# SCH_CanSat2024_v5_1.net
KiCad netlist of a schematic drawn in EasyEDA
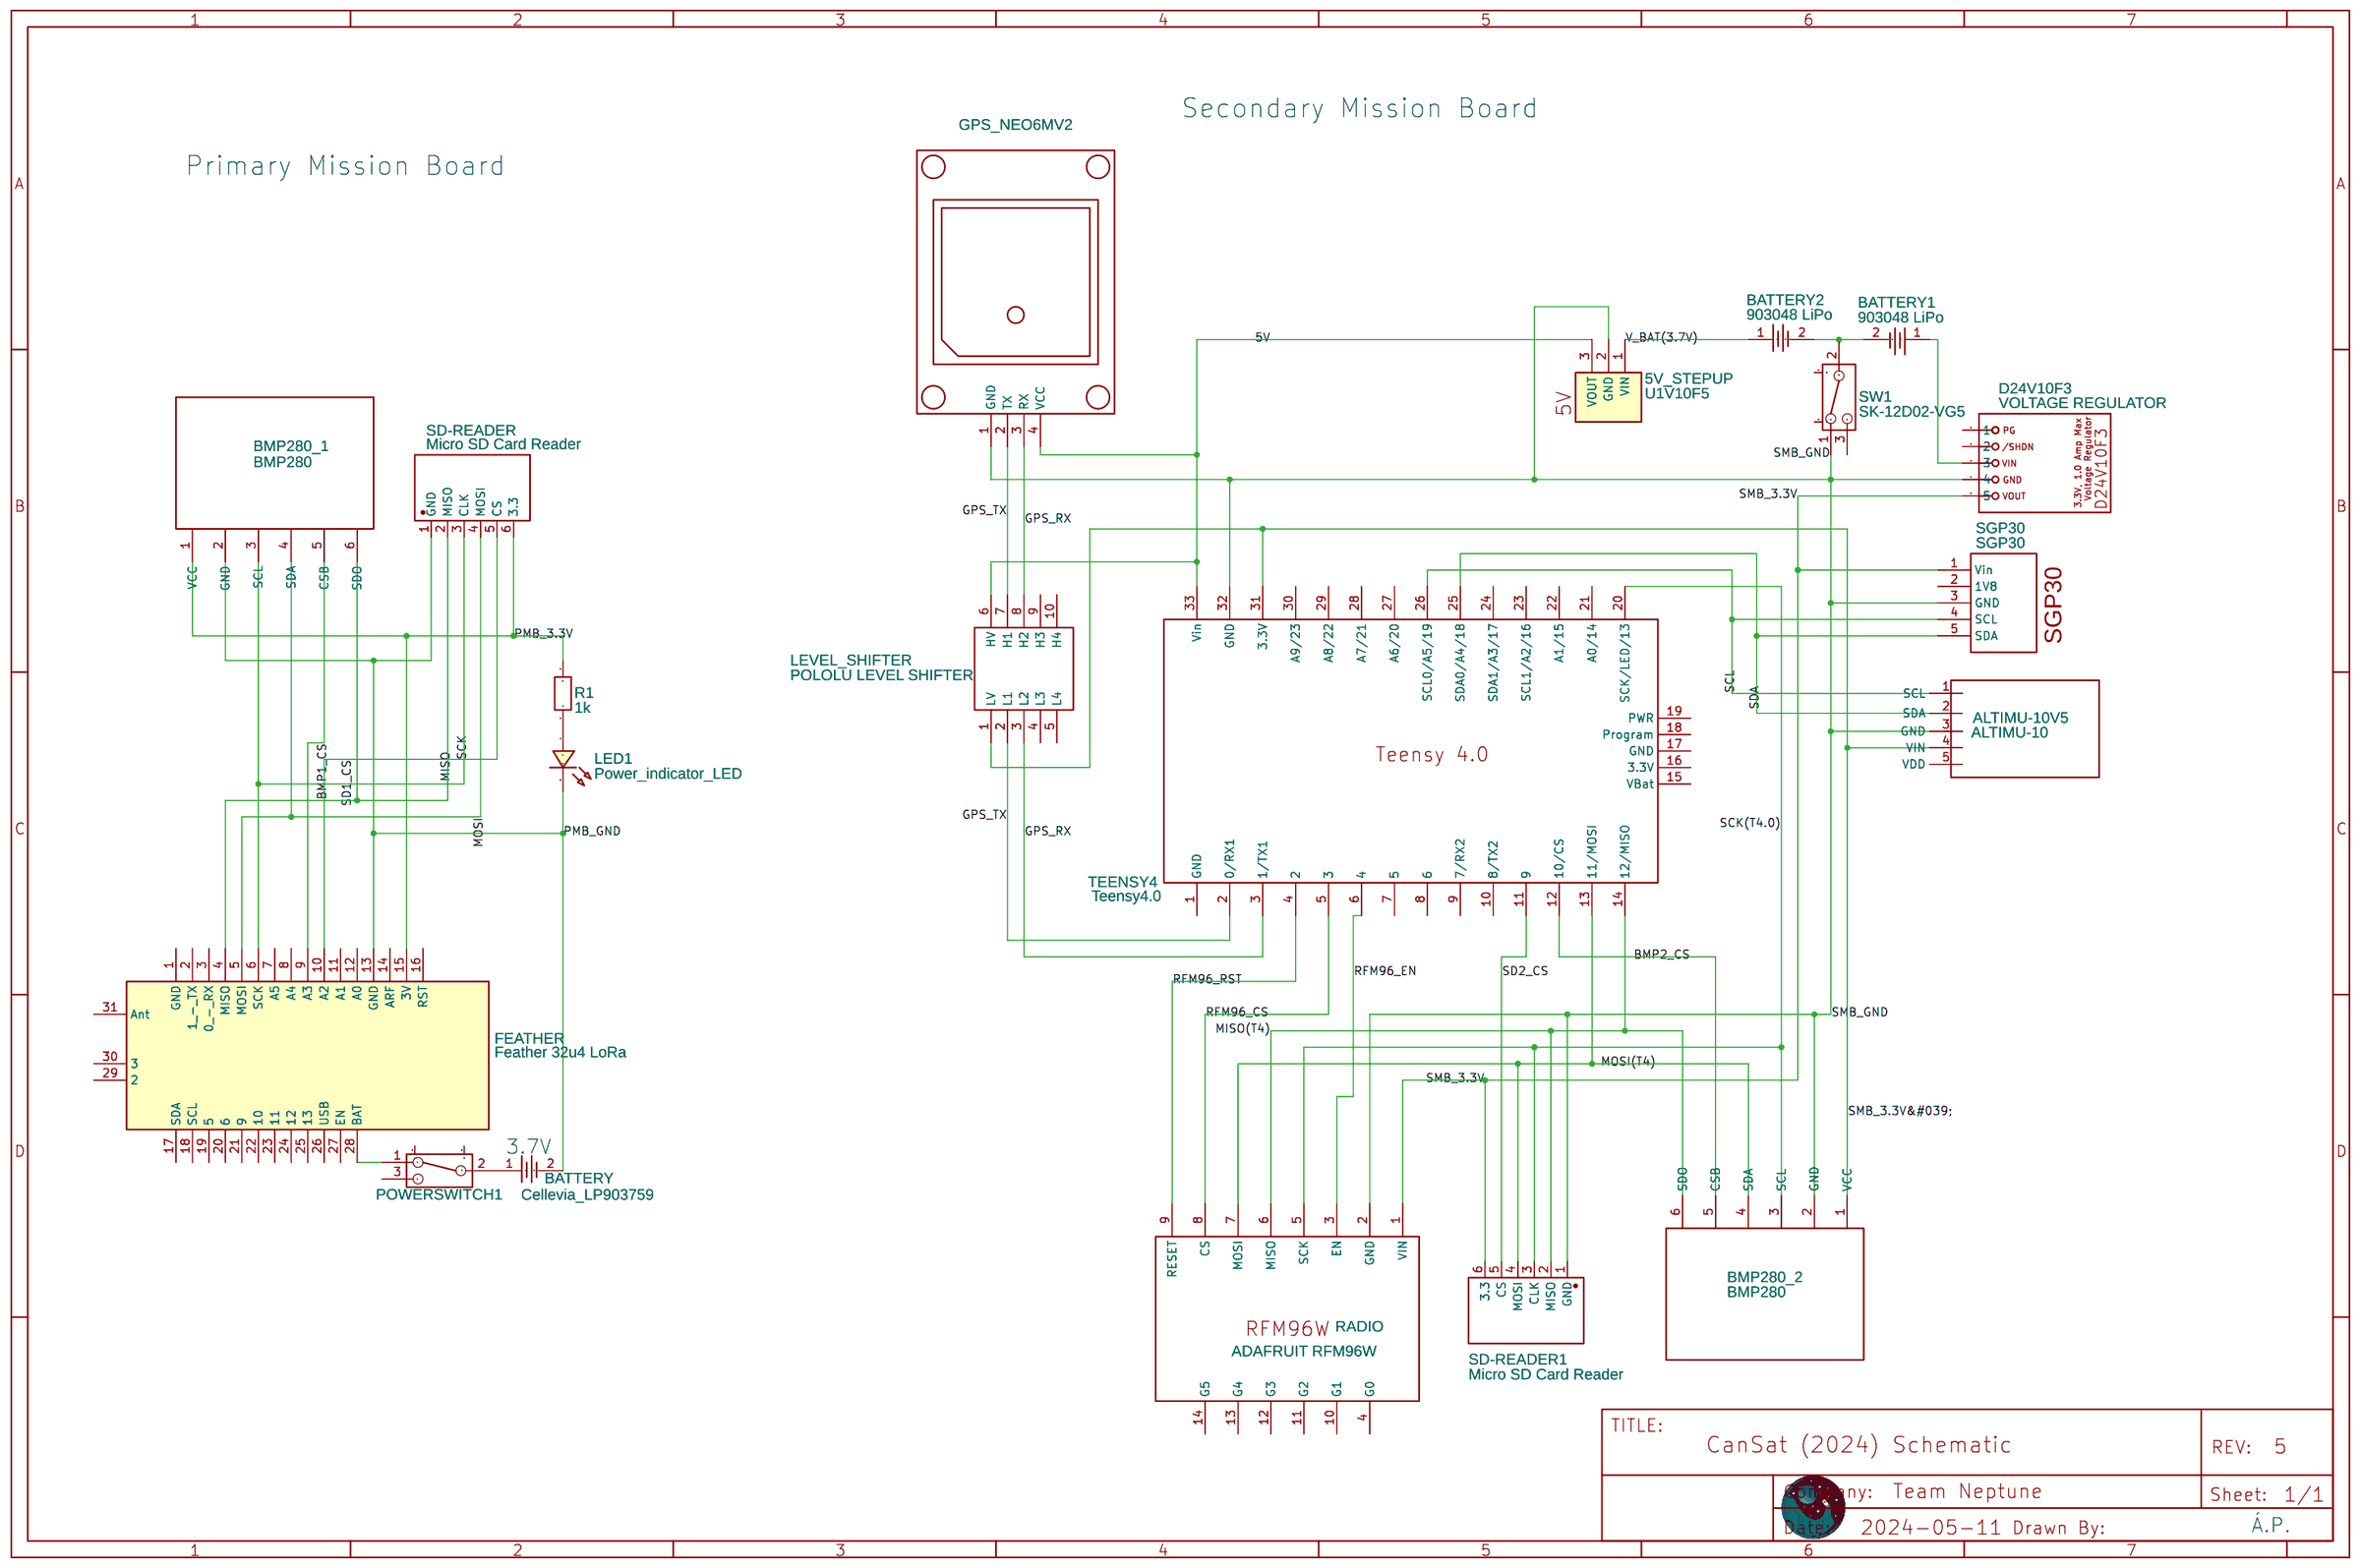
[diagram p0: schematic sheet]

(export (version "E")
  (design (tool "Eeschema 10.0.6"))
  (components
    (comp (ref "5V_STEPUP") (value "U1V10F5") (libsource (lib "") (part "U1V10F5 COPY")))
    (comp (ref "ALTIMU-10V5") (value "ALTIMU-10") (libsource (lib "") (part "ALTIMU-10")))
    (comp (ref "BATTERY")
      (value "Cellevia_LP903759")
      (fields (field (name "Manufacturer Part") "CR1220-2") (field (name "Manufacturer") "Q&J"))
      (libsource (lib "") (part "CR1220-2"))
    )
    (comp (ref "BATTERY1")
      (value "903048 LiPo")
      (fields (field (name "Manufacturer Part") "CR1220-2") (field (name "Manufacturer") "Q&J"))
      (libsource (lib "") (part "CR1220-2_1"))
    )
    (comp (ref "BATTERY2")
      (value "903048 LiPo")
      (fields (field (name "Manufacturer Part") "CR1220-2") (field (name "Manufacturer") "Q&J"))
      (libsource (lib "") (part "CR1220-2"))
    )
    (comp (ref "BMP280_1") (value "BMP280") (libsource (lib "") (part "BMP280_1")))
    (comp (ref "BMP280_2") (value "BMP280") (libsource (lib "") (part "BMP280")))
    (comp (ref "D24V10F3")
      (value "VOLTAGE REGULATOR")
      (fields (field (name "Manufacturer Part") "HDR-M-2.54_1x6"))
      (libsource (lib "") (part "D24V10F5 VOLTAGE REGULATOR"))
    )
    (comp (ref "FEATHER") (value "Feather 32u4 LoRa") (libsource (lib "") (part "Feather 32u4 LoRa")))
    (comp (ref "GPS_NEO6MV2") (value "Cheap GPS") (libsource (lib "") (part "Cheap GPS")))
    (comp (ref "LED1")
      (value "Power_indicator_LED")
      (fields
        (field (name "Manufacturer Part") "19-217/R6C-AL1M2VY/3T")
        (field (name "Manufacturer") "EVERLIGHT(台湾亿光)")
      )
      (libsource (lib "") (part "LED-0603_R"))
    )
    (comp (ref "LEVEL_SHIFTER")
      (value "POLOLU LEVEL SHIFTER")
      (fields (field (name "Manufacturer Part") "pololu #2595") (field (name "Manufacturer") "POLOLU"))
      (libsource (lib "") (part "pololu_level_shifter"))
    )
    (comp (ref "POWERSWITCH1")
      (value "SWITCH")
      (fields
        (field (name "Manufacturer Part") "SK-12D02-VG5")
        (field (name "Manufacturer") "Rectangular Connectors - Contacts")
      )
      (libsource (lib "") (part "SK-12D02-VG5_1"))
    )
    (comp (ref "R1") (value "1k") (libsource (lib "") (part "R_0603_EU")))
    (comp (ref "RADIO")
      (value "ADAFRUIT RFM96W")
      (fields (field (name "Manufacturer Part") "RFM96W") (field (name "Manufacturer") "HopeRF"))
      (libsource (lib "") (part "ADAFRUIT RFM96W BOARD COPY"))
    )
    (comp (ref "SD-READER")
      (value "Micro SD Card Reader")
      (fields
        (field (name "Manufacturer Part") "SD card reader 17.9x17.9")
        (field (name "Manufacturer") "ShengYang")
      )
      (libsource (lib "") (part "Micro SD Card Reader_1"))
    )
    (comp (ref "SD-READER1")
      (value "Micro SD Card Reader")
      (fields
        (field (name "Manufacturer Part") "SD card reader 17.9x17.9")
        (field (name "Manufacturer") "ShengYang")
      )
      (libsource (lib "") (part "Micro SD Card Reader"))
    )
    (comp (ref "SGP30")
      (value "SGP30")
      (fields (field (name "Manufacturer Part") "Adafruit"))
      (libsource (lib "") (part "SGP30"))
    )
    (comp (ref "SW1")
      (value "SK-12D02-VG5")
      (fields (field (name "Manufacturer") "Rectangular Connectors - Contacts"))
      (libsource (lib "") (part "SK-12D02-VG5"))
    )
    (comp (ref "TEENSY4")
      (value "Teensy4.0")
      (fields (field (name "Manufacturer") "PJRC"))
      (libsource (lib "") (part "Teensy4.0"))
    )
  )
  (nets
    (net (code "1") (name "/5V") (class "Default")
      (node (ref "5V_STEPUP") (pin "3") (pinfunction "VOUT_3") (pintype "unspecified"))
      (node (ref "GPS_NEO6MV2") (pin "4") (pinfunction "VCC_4") (pintype "unspecified"))
      (node (ref "LEVEL_SHIFTER") (pin "6") (pinfunction "HV_6") (pintype "unspecified"))
      (node (ref "TEENSY4") (pin "33") (pinfunction "Vin_33") (pintype "unspecified"))
    )
    (net (code "2") (name "/BMP1_CS") (class "Default")
      (node (ref "BMP280_1") (pin "5") (pinfunction "CSB_5") (pintype "unspecified"))
      (node (ref "FEATHER") (pin "9") (pinfunction "A3_9") (pintype "unspecified"))
    )
    (net (code "3") (name "/BMP2_CS") (class "Default")
      (node (ref "BMP280_2") (pin "5") (pinfunction "CSB_5") (pintype "unspecified"))
      (node (ref "TEENSY4") (pin "12") (pinfunction "10/CS_12") (pintype "unspecified"))
    )
    (net (code "4") (name "/GPS_RX") (class "Default")
      (node (ref "GPS_NEO6MV2") (pin "3") (pinfunction "RX_3") (pintype "unspecified"))
      (node (ref "LEVEL_SHIFTER") (pin "3") (pinfunction "L2_3") (pintype "unspecified"))
      (node (ref "LEVEL_SHIFTER") (pin "8") (pinfunction "H2_8") (pintype "unspecified"))
      (node (ref "TEENSY4") (pin "3") (pinfunction "1/TX1_3") (pintype "unspecified"))
    )
    (net (code "5") (name "/GPS_TX") (class "Default")
      (node (ref "GPS_NEO6MV2") (pin "2") (pinfunction "TX_2") (pintype "unspecified"))
      (node (ref "LEVEL_SHIFTER") (pin "2") (pinfunction "L1_2") (pintype "unspecified"))
      (node (ref "LEVEL_SHIFTER") (pin "7") (pinfunction "H1_7") (pintype "unspecified"))
      (node (ref "TEENSY4") (pin "2") (pinfunction "0/RX1_2") (pintype "unspecified"))
    )
    (net (code "6") (name "/MISO") (class "Default")
      (node (ref "BMP280_1") (pin "6") (pinfunction "SDO_6") (pintype "unspecified"))
      (node (ref "FEATHER") (pin "4") (pinfunction "MISO_4") (pintype "unspecified"))
      (node (ref "SD-READER") (pin "2") (pinfunction "MISO_2") (pintype "unspecified"))
    )
    (net (code "7") (name "/MISO(T4)") (class "Default")
      (node (ref "BMP280_2") (pin "6") (pinfunction "SDO_6") (pintype "unspecified"))
      (node (ref "RADIO") (pin "6") (pinfunction "MISO_6") (pintype "unspecified"))
      (node (ref "SD-READER1") (pin "2") (pinfunction "MISO_2") (pintype "unspecified"))
      (node (ref "TEENSY4") (pin "14") (pinfunction "12/MISO_14") (pintype "unspecified"))
    )
    (net (code "8") (name "/MOSI") (class "Default")
      (node (ref "BMP280_1") (pin "4") (pinfunction "SDA_4") (pintype "unspecified"))
      (node (ref "FEATHER") (pin "5") (pinfunction "MOSI_5") (pintype "unspecified"))
      (node (ref "SD-READER") (pin "4") (pinfunction "MOSI_4") (pintype "unspecified"))
    )
    (net (code "9") (name "/MOSI(T4)") (class "Default")
      (node (ref "BMP280_2") (pin "4") (pinfunction "SDA_4") (pintype "unspecified"))
      (node (ref "RADIO") (pin "7") (pinfunction "MOSI_7") (pintype "unspecified"))
      (node (ref "SD-READER1") (pin "4") (pinfunction "MOSI_4") (pintype "unspecified"))
      (node (ref "TEENSY4") (pin "13") (pinfunction "11/MOSI_13") (pintype "unspecified"))
    )
    (net (code "10") (name "/PMB_3.3V") (class "Default")
      (node (ref "BMP280_1") (pin "1") (pinfunction "VCC_1") (pintype "unspecified"))
      (node (ref "FEATHER") (pin "15") (pinfunction "3V_15") (pintype "unspecified"))
      (node (ref "R1") (pin "2") (pinfunction "2_2") (pintype "unspecified"))
      (node (ref "SD-READER") (pin "6") (pinfunction "3.3_6") (pintype "unspecified"))
    )
    (net (code "11") (name "/PMB_GND") (class "Default")
      (node (ref "BATTERY") (pin "2") (pinfunction "2_2") (pintype "input"))
      (node (ref "BMP280_1") (pin "2") (pinfunction "GND_2") (pintype "unspecified"))
      (node (ref "FEATHER") (pin "13") (pinfunction "GND_13") (pintype "unspecified"))
      (node (ref "LED1") (pin "2") (pinfunction "2_2") (pintype "unspecified"))
      (node (ref "SD-READER") (pin "1") (pinfunction "GND_1") (pintype "unspecified"))
    )
    (net (code "12") (name "/RFM96_CS") (class "Default")
      (node (ref "RADIO") (pin "8") (pinfunction "CS_8") (pintype "unspecified"))
      (node (ref "TEENSY4") (pin "5") (pinfunction "3_5") (pintype "unspecified"))
    )
    (net (code "13") (name "/RFM96_EN") (class "Default")
      (node (ref "RADIO") (pin "3") (pinfunction "EN_3") (pintype "unspecified"))
      (node (ref "TEENSY4") (pin "6") (pinfunction "4_6") (pintype "unspecified"))
    )
    (net (code "14") (name "/RFM96_RST") (class "Default")
      (node (ref "RADIO") (pin "9") (pinfunction "RESET_9") (pintype "unspecified"))
      (node (ref "TEENSY4") (pin "4") (pinfunction "2_4") (pintype "unspecified"))
    )
    (net (code "15") (name "/SCK") (class "Default")
      (node (ref "BMP280_1") (pin "3") (pinfunction "SCL_3") (pintype "unspecified"))
      (node (ref "FEATHER") (pin "6") (pinfunction "SCK_6") (pintype "unspecified"))
      (node (ref "SD-READER") (pin "3") (pinfunction "CLK_3") (pintype "unspecified"))
    )
    (net (code "16") (name "/SCK(T4.0)") (class "Default")
      (node (ref "BMP280_2") (pin "3") (pinfunction "SCL_3") (pintype "unspecified"))
      (node (ref "RADIO") (pin "5") (pinfunction "SCK_5") (pintype "unspecified"))
      (node (ref "SD-READER1") (pin "3") (pinfunction "CLK_3") (pintype "unspecified"))
      (node (ref "TEENSY4") (pin "20") (pinfunction "SCK/LED/13_20") (pintype "unspecified"))
    )
    (net (code "17") (name "/SCL") (class "Default")
      (node (ref "ALTIMU-10V5") (pin "1") (pinfunction "SCL_1") (pintype "unspecified"))
      (node (ref "SGP30") (pin "4") (pinfunction "SCL_4") (pintype "unspecified"))
      (node (ref "TEENSY4") (pin "26") (pinfunction "SCL0/A5/19_26") (pintype "unspecified"))
    )
    (net (code "18") (name "/SD1_CS") (class "Default")
      (node (ref "FEATHER") (pin "10") (pinfunction "A2_10") (pintype "unspecified"))
      (node (ref "SD-READER") (pin "5") (pinfunction "CS_5") (pintype "unspecified"))
    )
    (net (code "19") (name "/SD2_CS") (class "Default")
      (node (ref "SD-READER1") (pin "5") (pinfunction "CS_5") (pintype "unspecified"))
      (node (ref "TEENSY4") (pin "11") (pinfunction "9_11") (pintype "unspecified"))
    )
    (net (code "20") (name "/SDA") (class "Default")
      (node (ref "ALTIMU-10V5") (pin "2") (pinfunction "SDA_2") (pintype "unspecified"))
      (node (ref "SGP30") (pin "5") (pinfunction "SDA_5") (pintype "unspecified"))
      (node (ref "TEENSY4") (pin "25") (pinfunction "SDA0/A4/18_25") (pintype "unspecified"))
    )
    (net (code "21") (name "/SMB_3.3V") (class "Default")
      (node (ref "D24V10F3") (pin "5") (pinfunction "5_5") (pintype "unspecified"))
      (node (ref "RADIO") (pin "1") (pinfunction "VIN_1") (pintype "unspecified"))
      (node (ref "SD-READER1") (pin "6") (pinfunction "3.3_6") (pintype "unspecified"))
      (node (ref "SGP30") (pin "1") (pinfunction "Vin_1") (pintype "unspecified"))
    )
    (net (code "22") (name "/SMB_3.3V&#039;") (class "Default")
      (node (ref "ALTIMU-10V5") (pin "4") (pinfunction "VIN_4") (pintype "unspecified"))
      (node (ref "BMP280_2") (pin "1") (pinfunction "VCC_1") (pintype "unspecified"))
      (node (ref "LEVEL_SHIFTER") (pin "1") (pinfunction "LV_1") (pintype "unspecified"))
      (node (ref "TEENSY4") (pin "31") (pinfunction "3.3V_31") (pintype "unspecified"))
    )
    (net (code "23") (name "/SMB_GND") (class "Default")
      (node (ref "5V_STEPUP") (pin "2") (pinfunction "GND_2") (pintype "unspecified"))
      (node (ref "ALTIMU-10V5") (pin "3") (pinfunction "GND_3") (pintype "unspecified"))
      (node (ref "BMP280_2") (pin "2") (pinfunction "GND_2") (pintype "unspecified"))
      (node (ref "D24V10F3") (pin "4") (pinfunction "4_4") (pintype "unspecified"))
      (node (ref "GPS_NEO6MV2") (pin "1") (pinfunction "GND_1") (pintype "unspecified"))
      (node (ref "RADIO") (pin "2") (pinfunction "GND_2") (pintype "unspecified"))
      (node (ref "SD-READER1") (pin "1") (pinfunction "GND_1") (pintype "unspecified"))
      (node (ref "SGP30") (pin "3") (pinfunction "GND_3") (pintype "unspecified"))
      (node (ref "SW1") (pin "1") (pinfunction "1_1") (pintype "unspecified"))
      (node (ref "TEENSY4") (pin "32") (pinfunction "GND_32") (pintype "unspecified"))
    )
    (net (code "24") (name "/V_BAT(3.7V)") (class "Default")
      (node (ref "5V_STEPUP") (pin "1") (pinfunction "VIN_1") (pintype "unspecified"))
      (node (ref "BATTERY2") (pin "1") (pinfunction "1_1") (pintype "input"))
    )
    (net (code "25") (name "Net-(BATTERY-Pad1)") (class "Default")
      (node (ref "BATTERY") (pin "1") (pinfunction "1_1") (pintype "input"))
      (node (ref "POWERSWITCH1") (pin "2") (pinfunction "2_2") (pintype "unspecified"))
    )
    (net (code "26") (name "Net-(BATTERY1-Pad1)") (class "Default")
      (node (ref "BATTERY1") (pin "1") (pinfunction "1_1") (pintype "input"))
      (node (ref "D24V10F3") (pin "3") (pinfunction "3_3") (pintype "unspecified"))
    )
    (net (code "27") (name "Net-(BATTERY1-Pad2)") (class "Default")
      (node (ref "BATTERY1") (pin "2") (pinfunction "2_2") (pintype "input"))
      (node (ref "BATTERY2") (pin "2") (pinfunction "2_2") (pintype "input"))
      (node (ref "SW1") (pin "2") (pinfunction "2_2") (pintype "unspecified"))
    )
    (net (code "28") (name "Net-(FEATHER-BAT)") (class "Default")
      (node (ref "FEATHER") (pin "28") (pinfunction "BAT_28") (pintype "unspecified"))
      (node (ref "POWERSWITCH1") (pin "1") (pinfunction "1_1") (pintype "unspecified"))
    )
    (net (code "29") (name "Net-(LED1-Pad1)") (class "Default")
      (node (ref "LED1") (pin "1") (pinfunction "1_1") (pintype "unspecified"))
      (node (ref "R1") (pin "1") (pinfunction "1_1") (pintype "unspecified"))
    )
    (net (code "30") (name "unconnected-(ALTIMU-10V5-VDD-Pad5)") (class "Default")
      (node (ref "ALTIMU-10V5") (pin "5") (pinfunction "VDD_5") (pintype "unspecified"))
    )
    (net (code "31") (name "unconnected-(D24V10F3-Pad1)") (class "Default")
      (node (ref "D24V10F3") (pin "1") (pinfunction "1_1") (pintype "unspecified"))
    )
    (net (code "32") (name "unconnected-(D24V10F3-Pad2)") (class "Default")
      (node (ref "D24V10F3") (pin "2") (pinfunction "2_2") (pintype "unspecified"))
    )
    (net (code "33") (name "unconnected-(FEATHER-0_-_RX-Pad3)") (class "Default")
      (node (ref "FEATHER") (pin "3") (pinfunction "0_-_RX_3") (pintype "unspecified"))
    )
    (net (code "34") (name "unconnected-(FEATHER-1_-_TX-Pad2)") (class "Default")
      (node (ref "FEATHER") (pin "2") (pinfunction "1_-_TX_2") (pintype "unspecified"))
    )
    (net (code "35") (name "unconnected-(FEATHER-2-Pad29)") (class "Default")
      (node (ref "FEATHER") (pin "29") (pinfunction "2_29") (pintype "unspecified"))
    )
    (net (code "36") (name "unconnected-(FEATHER-3-Pad30)") (class "Default")
      (node (ref "FEATHER") (pin "30") (pinfunction "3_30") (pintype "unspecified"))
    )
    (net (code "37") (name "unconnected-(FEATHER-5-Pad19)") (class "Default")
      (node (ref "FEATHER") (pin "19") (pinfunction "5_19") (pintype "unspecified"))
    )
    (net (code "38") (name "unconnected-(FEATHER-6-Pad20)") (class "Default")
      (node (ref "FEATHER") (pin "20") (pinfunction "6_20") (pintype "unspecified"))
    )
    (net (code "39") (name "unconnected-(FEATHER-9-Pad21)") (class "Default")
      (node (ref "FEATHER") (pin "21") (pinfunction "9_21") (pintype "unspecified"))
    )
    (net (code "40") (name "unconnected-(FEATHER-10-Pad22)") (class "Default")
      (node (ref "FEATHER") (pin "22") (pinfunction "10_22") (pintype "unspecified"))
    )
    (net (code "41") (name "unconnected-(FEATHER-11-Pad23)") (class "Default")
      (node (ref "FEATHER") (pin "23") (pinfunction "11_23") (pintype "unspecified"))
    )
    (net (code "42") (name "unconnected-(FEATHER-12-Pad24)") (class "Default")
      (node (ref "FEATHER") (pin "24") (pinfunction "12_24") (pintype "unspecified"))
    )
    (net (code "43") (name "unconnected-(FEATHER-13-Pad25)") (class "Default")
      (node (ref "FEATHER") (pin "25") (pinfunction "13_25") (pintype "unspecified"))
    )
    (net (code "44") (name "unconnected-(FEATHER-A0-Pad12)") (class "Default")
      (node (ref "FEATHER") (pin "12") (pinfunction "A0_12") (pintype "unspecified"))
    )
    (net (code "45") (name "unconnected-(FEATHER-A1-Pad11)") (class "Default")
      (node (ref "FEATHER") (pin "11") (pinfunction "A1_11") (pintype "unspecified"))
    )
    (net (code "46") (name "unconnected-(FEATHER-A4-Pad8)") (class "Default")
      (node (ref "FEATHER") (pin "8") (pinfunction "A4_8") (pintype "unspecified"))
    )
    (net (code "47") (name "unconnected-(FEATHER-A5-Pad7)") (class "Default")
      (node (ref "FEATHER") (pin "7") (pinfunction "A5_7") (pintype "unspecified"))
    )
    (net (code "48") (name "unconnected-(FEATHER-ARF-Pad14)") (class "Default")
      (node (ref "FEATHER") (pin "14") (pinfunction "ARF_14") (pintype "unspecified"))
    )
    (net (code "49") (name "unconnected-(FEATHER-Ant-Pad31)") (class "Default")
      (node (ref "FEATHER") (pin "31") (pinfunction "Ant_31") (pintype "unspecified"))
    )
    (net (code "50") (name "unconnected-(FEATHER-EN-Pad27)") (class "Default")
      (node (ref "FEATHER") (pin "27") (pinfunction "EN_27") (pintype "unspecified"))
    )
    (net (code "51") (name "unconnected-(FEATHER-GND-Pad1)") (class "Default")
      (node (ref "FEATHER") (pin "1") (pinfunction "GND_1") (pintype "unspecified"))
    )
    (net (code "52") (name "unconnected-(FEATHER-RST-Pad16)") (class "Default")
      (node (ref "FEATHER") (pin "16") (pinfunction "RST_16") (pintype "unspecified"))
    )
    (net (code "53") (name "unconnected-(FEATHER-SCL-Pad18)") (class "Default")
      (node (ref "FEATHER") (pin "18") (pinfunction "SCL_18") (pintype "unspecified"))
    )
    (net (code "54") (name "unconnected-(FEATHER-SDA-Pad17)") (class "Default")
      (node (ref "FEATHER") (pin "17") (pinfunction "SDA_17") (pintype "unspecified"))
    )
    (net (code "55") (name "unconnected-(FEATHER-USB-Pad26)") (class "Default")
      (node (ref "FEATHER") (pin "26") (pinfunction "USB_26") (pintype "unspecified"))
    )
    (net (code "56") (name "unconnected-(LEVEL_SHIFTER-H3-Pad9)") (class "Default")
      (node (ref "LEVEL_SHIFTER") (pin "9") (pinfunction "H3_9") (pintype "unspecified"))
    )
    (net (code "57") (name "unconnected-(LEVEL_SHIFTER-H4-Pad10)") (class "Default")
      (node (ref "LEVEL_SHIFTER") (pin "10") (pinfunction "H4_10") (pintype "unspecified"))
    )
    (net (code "58") (name "unconnected-(LEVEL_SHIFTER-L3-Pad4)") (class "Default")
      (node (ref "LEVEL_SHIFTER") (pin "4") (pinfunction "L3_4") (pintype "unspecified"))
    )
    (net (code "59") (name "unconnected-(LEVEL_SHIFTER-L4-Pad5)") (class "Default")
      (node (ref "LEVEL_SHIFTER") (pin "5") (pinfunction "L4_5") (pintype "unspecified"))
    )
    (net (code "60") (name "unconnected-(POWERSWITCH1-Pad3)") (class "Default")
      (node (ref "POWERSWITCH1") (pin "3") (pinfunction "3_3") (pintype "unspecified"))
    )
    (net (code "61") (name "unconnected-(POWERSWITCH1-Pad4)") (class "Default")
      (node (ref "POWERSWITCH1") (pin "4") (pinfunction "4_4") (pintype "unspecified"))
    )
    (net (code "62") (name "unconnected-(POWERSWITCH1-Pad5)") (class "Default")
      (node (ref "POWERSWITCH1") (pin "5") (pinfunction "5_5") (pintype "unspecified"))
    )
    (net (code "63") (name "unconnected-(RADIO-G0-Pad4)") (class "Default")
      (node (ref "RADIO") (pin "4") (pinfunction "G0_4") (pintype "unspecified"))
    )
    (net (code "64") (name "unconnected-(RADIO-G1-Pad10)") (class "Default")
      (node (ref "RADIO") (pin "10") (pinfunction "G1_10") (pintype "unspecified"))
    )
    (net (code "65") (name "unconnected-(RADIO-G2-Pad11)") (class "Default")
      (node (ref "RADIO") (pin "11") (pinfunction "G2_11") (pintype "unspecified"))
    )
    (net (code "66") (name "unconnected-(RADIO-G3-Pad12)") (class "Default")
      (node (ref "RADIO") (pin "12") (pinfunction "G3_12") (pintype "unspecified"))
    )
    (net (code "67") (name "unconnected-(RADIO-G4-Pad13)") (class "Default")
      (node (ref "RADIO") (pin "13") (pinfunction "G4_13") (pintype "unspecified"))
    )
    (net (code "68") (name "unconnected-(RADIO-G5-Pad14)") (class "Default")
      (node (ref "RADIO") (pin "14") (pinfunction "G5_14") (pintype "unspecified"))
    )
    (net (code "69") (name "unconnected-(SGP30-1V8-Pad2)") (class "Default")
      (node (ref "SGP30") (pin "2") (pinfunction "1V8_2") (pintype "unspecified"))
    )
    (net (code "70") (name "unconnected-(SW1-Pad3)") (class "Default")
      (node (ref "SW1") (pin "3") (pinfunction "3_3") (pintype "unspecified"))
    )
    (net (code "71") (name "unconnected-(SW1-Pad4)") (class "Default")
      (node (ref "SW1") (pin "4") (pinfunction "4_4") (pintype "unspecified"))
    )
    (net (code "72") (name "unconnected-(SW1-Pad5)") (class "Default")
      (node (ref "SW1") (pin "5") (pinfunction "5_5") (pintype "unspecified"))
    )
    (net (code "73") (name "unconnected-(TEENSY4-3.3V-Pad16)") (class "Default")
      (node (ref "TEENSY4") (pin "16") (pinfunction "3.3V_16") (pintype "unspecified"))
    )
    (net (code "74") (name "unconnected-(TEENSY4-5-Pad7)") (class "Default")
      (node (ref "TEENSY4") (pin "7") (pinfunction "5_7") (pintype "unspecified"))
    )
    (net (code "75") (name "unconnected-(TEENSY4-6-Pad8)") (class "Default")
      (node (ref "TEENSY4") (pin "8") (pinfunction "6_8") (pintype "unspecified"))
    )
    (net (code "76") (name "unconnected-(TEENSY4-7{slash}RX2-Pad9)") (class "Default")
      (node (ref "TEENSY4") (pin "9") (pinfunction "7/RX2_9") (pintype "unspecified"))
    )
    (net (code "77") (name "unconnected-(TEENSY4-8{slash}TX2-Pad10)") (class "Default")
      (node (ref "TEENSY4") (pin "10") (pinfunction "8/TX2_10") (pintype "unspecified"))
    )
    (net (code "78") (name "unconnected-(TEENSY4-A0{slash}14-Pad21)") (class "Default")
      (node (ref "TEENSY4") (pin "21") (pinfunction "A0/14_21") (pintype "unspecified"))
    )
    (net (code "79") (name "unconnected-(TEENSY4-A1{slash}15-Pad22)") (class "Default")
      (node (ref "TEENSY4") (pin "22") (pinfunction "A1/15_22") (pintype "unspecified"))
    )
    (net (code "80") (name "unconnected-(TEENSY4-A6{slash}20-Pad27)") (class "Default")
      (node (ref "TEENSY4") (pin "27") (pinfunction "A6/20_27") (pintype "unspecified"))
    )
    (net (code "81") (name "unconnected-(TEENSY4-A7{slash}21-Pad28)") (class "Default")
      (node (ref "TEENSY4") (pin "28") (pinfunction "A7/21_28") (pintype "unspecified"))
    )
    (net (code "82") (name "unconnected-(TEENSY4-A8{slash}22-Pad29)") (class "Default")
      (node (ref "TEENSY4") (pin "29") (pinfunction "A8/22_29") (pintype "unspecified"))
    )
    (net (code "83") (name "unconnected-(TEENSY4-A9{slash}23-Pad30)") (class "Default")
      (node (ref "TEENSY4") (pin "30") (pinfunction "A9/23_30") (pintype "unspecified"))
    )
    (net (code "84") (name "unconnected-(TEENSY4-GND-Pad1)") (class "Default")
      (node (ref "TEENSY4") (pin "1") (pinfunction "GND_1") (pintype "unspecified"))
    )
    (net (code "85") (name "unconnected-(TEENSY4-GND-Pad17)") (class "Default")
      (node (ref "TEENSY4") (pin "17") (pinfunction "GND_17") (pintype "unspecified"))
    )
    (net (code "86") (name "unconnected-(TEENSY4-PWR-Pad19)") (class "Default")
      (node (ref "TEENSY4") (pin "19") (pinfunction "PWR_19") (pintype "unspecified"))
    )
    (net (code "87") (name "unconnected-(TEENSY4-Program-Pad18)") (class "Default")
      (node (ref "TEENSY4") (pin "18") (pinfunction "Program_18") (pintype "unspecified"))
    )
    (net (code "88") (name "unconnected-(TEENSY4-SCL1{slash}A2{slash}16-Pad23)") (class "Default")
      (node (ref "TEENSY4") (pin "23") (pinfunction "SCL1/A2/16_23") (pintype "unspecified"))
    )
    (net (code "89") (name "unconnected-(TEENSY4-SDA1{slash}A3{slash}17-Pad24)") (class "Default")
      (node (ref "TEENSY4") (pin "24") (pinfunction "SDA1/A3/17_24") (pintype "unspecified"))
    )
    (net (code "90") (name "unconnected-(TEENSY4-VBat-Pad15)") (class "Default")
      (node (ref "TEENSY4") (pin "15") (pinfunction "VBat_15") (pintype "unspecified"))
    )
  )
)
